# Input.net
KiCad netlist of a schematic drawn in Altium Designer
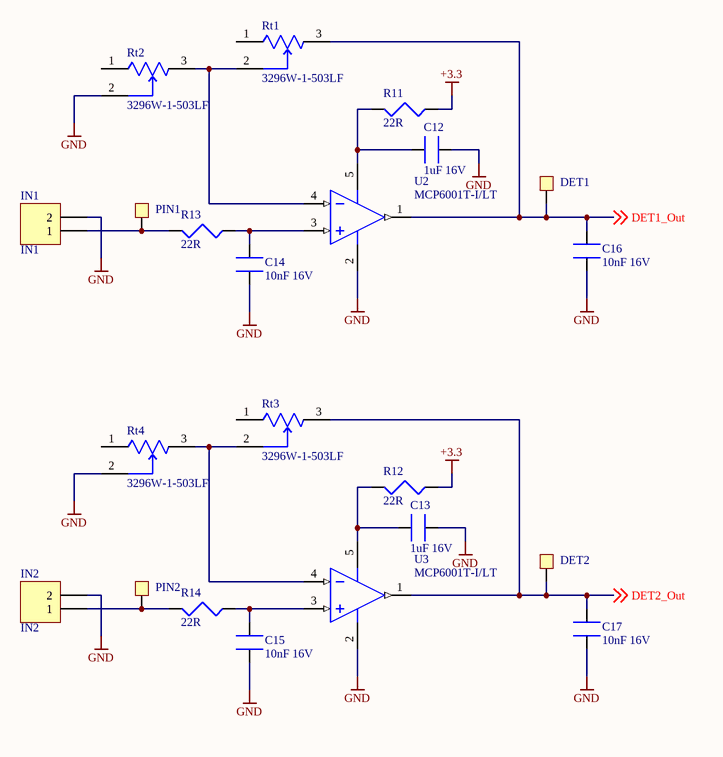
[diagram p0: Input.SchDoc]

(export (version "E")
  (design (tool "Eeschema 10.0.6"))
  (components
    (comp (ref "C12") (value "1uF 16V") (footprint "0805_C") (libsource (lib "Schlib1") (part "Cap")))
    (comp (ref "C13") (value "1uF 16V") (footprint "0805_C") (libsource (lib "Schlib1") (part "Cap")))
    (comp (ref "C14") (value "10nF 16V") (footprint "0805_C") (libsource (lib "Schlib1") (part "Cap")))
    (comp (ref "C15") (value "10nF 16V") (footprint "0805_C") (libsource (lib "Schlib1") (part "Cap")))
    (comp (ref "C16") (value "10nF 16V") (footprint "0805_C") (libsource (lib "Schlib1") (part "Cap")))
    (comp (ref "C17") (value "10nF 16V") (footprint "0805_C") (libsource (lib "Schlib1") (part "Cap")))
    (comp (ref "DET1") (value "Point") (footprint "Test_Point") (libsource (lib "Schlib1") (part "Point")))
    (comp (ref "DET2") (value "Point") (footprint "Test_Point") (libsource (lib "Schlib1") (part "Point")))
    (comp (ref "IN1")
      (value "IN1")
      (footprint "HDR1X2")
      (description "Header, 2-Pin")
      (fields (field (name "PUBLISHER") "Altium Limited"))
      (libsource (lib "Miscellaneous Connectors") (part "Header 2"))
    )
    (comp (ref "IN2")
      (value "IN2")
      (footprint "HDR1X2")
      (description "Header, 2-Pin")
      (fields (field (name "PUBLISHER") "Altium Limited"))
      (libsource (lib "Miscellaneous Connectors") (part "Header 2"))
    )
    (comp (ref "PIN1") (value "Point") (footprint "Test_Point") (libsource (lib "Schlib1") (part "Point")))
    (comp (ref "PIN2") (value "Point") (footprint "Test_Point") (libsource (lib "Schlib1") (part "Point")))
    (comp (ref "R11") (value "22R") (footprint "0805_R") (libsource (lib "Schlib1") (part "Res")))
    (comp (ref "R12") (value "22R") (footprint "0805_R") (libsource (lib "Schlib1") (part "Res")))
    (comp (ref "R13") (value "22R") (footprint "0805_R") (libsource (lib "Schlib1") (part "Res")))
    (comp (ref "R14") (value "22R") (footprint "0805_R") (libsource (lib "Schlib1") (part "Res")))
    (comp (ref "Rt1")
      (value "3296W-1-503LF")
      (footprint "FP-3296W-MFG")
      (description "TRIMMER 50K OHM 0.5W PC PIN TOP")
      (fields
        (field (name "MANUFACTURER") "Bourns")
        (field (name "OCTOPART") "https://octopart.com/3296w-1-504lf-bourns-143884")
      )
      (libsource (lib "Altium Content Vault") (part "8d460c8a6f7ec10b1759d1b9c49aa93"))
    )
    (comp (ref "Rt2")
      (value "3296W-1-503LF")
      (footprint "FP-3296W-MFG")
      (description "TRIMMER 50K OHM 0.5W PC PIN TOP")
      (fields
        (field (name "MANUFACTURER") "Bourns")
        (field (name "OCTOPART") "https://octopart.com/3296w-1-504lf-bourns-143884")
      )
      (libsource (lib "Altium Content Vault") (part "8d460c8a6f7ec10b1759d1b9c49aa93"))
    )
    (comp (ref "Rt3")
      (value "3296W-1-503LF")
      (footprint "FP-3296W-MFG")
      (description "TRIMMER 50K OHM 0.5W PC PIN TOP")
      (fields
        (field (name "MANUFACTURER") "Bourns")
        (field (name "OCTOPART") "https://octopart.com/3296w-1-504lf-bourns-143884")
      )
      (libsource (lib "Altium Content Vault") (part "8d460c8a6f7ec10b1759d1b9c49aa93"))
    )
    (comp (ref "Rt4")
      (value "3296W-1-503LF")
      (footprint "FP-3296W-MFG")
      (description "TRIMMER 50K OHM 0.5W PC PIN TOP")
      (fields
        (field (name "MANUFACTURER") "Bourns")
        (field (name "OCTOPART") "https://octopart.com/3296w-1-504lf-bourns-143884")
      )
      (libsource (lib "Altium Content Vault") (part "8d460c8a6f7ec10b1759d1b9c49aa93"))
    )
    (comp (ref "U2")
      (value "MCP6001T-I/LT")
      (footprint "SC70-LT5_M")
      (description "1 MHz, Low-Power Operational Amplifier, 5-Pin SC-70, Industrial Temperature, Tape and Reel")
      (libsource (lib "Altium Content Vault") (part "AMP-OPA-MCP6001-SOT5"))
    )
    (comp (ref "U3")
      (value "MCP6001T-I/LT")
      (footprint "SC70-LT5_M")
      (description "1 MHz, Low-Power Operational Amplifier, 5-Pin SC-70, Industrial Temperature, Tape and Reel")
      (libsource (lib "Altium Content Vault") (part "AMP-OPA-MCP6001-SOT5"))
    )
  )
  (nets
    (net (code "1") (name "+3.3") (class "Default")
      (node (ref "R11") (pin "2") (pinfunction "2_2") (pintype "passive"))
      (node (ref "R12") (pin "2") (pinfunction "2_2") (pintype "passive"))
    )
    (net (code "2") (name "DET1_Out") (class "Default")
      (node (ref "C16") (pin "1") (pinfunction "1_1") (pintype "passive"))
      (node (ref "DET1") (pin "1") (pinfunction "1_1") (pintype "passive"))
      (node (ref "Rt1") (pin "3") (pinfunction "CW_3") (pintype "passive"))
      (node (ref "U2") (pin "1") (pinfunction "VOUT_1") (pintype "output"))
    )
    (net (code "3") (name "DET2_Out") (class "Default")
      (node (ref "C17") (pin "1") (pinfunction "1_1") (pintype "passive"))
      (node (ref "DET2") (pin "1") (pinfunction "1_1") (pintype "passive"))
      (node (ref "Rt3") (pin "3") (pinfunction "CW_3") (pintype "passive"))
      (node (ref "U3") (pin "1") (pinfunction "VOUT_1") (pintype "output"))
    )
    (net (code "4") (name "GND") (class "Default")
      (node (ref "C12") (pin "2") (pinfunction "2_2") (pintype "passive"))
      (node (ref "C13") (pin "2") (pinfunction "2_2") (pintype "passive"))
      (node (ref "C14") (pin "2") (pinfunction "2_2") (pintype "passive"))
      (node (ref "C15") (pin "2") (pinfunction "2_2") (pintype "passive"))
      (node (ref "C16") (pin "2") (pinfunction "2_2") (pintype "passive"))
      (node (ref "C17") (pin "2") (pinfunction "2_2") (pintype "passive"))
      (node (ref "IN1") (pin "2") (pinfunction "2_2") (pintype "passive"))
      (node (ref "IN2") (pin "2") (pinfunction "2_2") (pintype "passive"))
      (node (ref "Rt2") (pin "2") (pinfunction "WIPER_2") (pintype "passive"))
      (node (ref "Rt4") (pin "2") (pinfunction "WIPER_2") (pintype "passive"))
      (node (ref "U2") (pin "2") (pinfunction "VSS_2") (pintype "power_in"))
      (node (ref "U3") (pin "2") (pinfunction "VSS_2") (pintype "power_in"))
    )
    (net (code "5") (name "Net-(IN1-Pad1)") (class "Default")
      (node (ref "IN1") (pin "1") (pinfunction "1_1") (pintype "passive"))
      (node (ref "PIN1") (pin "1") (pinfunction "1_1") (pintype "passive"))
      (node (ref "R13") (pin "1") (pinfunction "1_1") (pintype "passive"))
    )
    (net (code "6") (name "Net-(IN2-Pad1)") (class "Default")
      (node (ref "IN2") (pin "1") (pinfunction "1_1") (pintype "passive"))
      (node (ref "PIN2") (pin "1") (pinfunction "1_1") (pintype "passive"))
      (node (ref "R14") (pin "1") (pinfunction "1_1") (pintype "passive"))
    )
    (net (code "7") (name "Net-(Rt1-WIPER)") (class "Default")
      (node (ref "Rt1") (pin "2") (pinfunction "WIPER_2") (pintype "passive"))
      (node (ref "Rt2") (pin "3") (pinfunction "CW_3") (pintype "passive"))
      (node (ref "U2") (pin "4") (pinfunction "VIN-_4") (pintype "input"))
    )
    (net (code "8") (name "Net-(Rt3-WIPER)") (class "Default")
      (node (ref "Rt3") (pin "2") (pinfunction "WIPER_2") (pintype "passive"))
      (node (ref "Rt4") (pin "3") (pinfunction "CW_3") (pintype "passive"))
      (node (ref "U3") (pin "4") (pinfunction "VIN-_4") (pintype "input"))
    )
    (net (code "9") (name "Net-(U2-VDD)") (class "Default")
      (node (ref "C12") (pin "1") (pinfunction "1_1") (pintype "passive"))
      (node (ref "R11") (pin "1") (pinfunction "1_1") (pintype "passive"))
      (node (ref "U2") (pin "5") (pinfunction "VDD_5") (pintype "power_in"))
    )
    (net (code "10") (name "Net-(U2-VIN+)") (class "Default")
      (node (ref "C14") (pin "1") (pinfunction "1_1") (pintype "passive"))
      (node (ref "R13") (pin "2") (pinfunction "2_2") (pintype "passive"))
      (node (ref "U2") (pin "3") (pinfunction "VIN+_3") (pintype "input"))
    )
    (net (code "11") (name "Net-(U3-VDD)") (class "Default")
      (node (ref "C13") (pin "1") (pinfunction "1_1") (pintype "passive"))
      (node (ref "R12") (pin "1") (pinfunction "1_1") (pintype "passive"))
      (node (ref "U3") (pin "5") (pinfunction "VDD_5") (pintype "power_in"))
    )
    (net (code "12") (name "Net-(U3-VIN+)") (class "Default")
      (node (ref "C15") (pin "1") (pinfunction "1_1") (pintype "passive"))
      (node (ref "R14") (pin "2") (pinfunction "2_2") (pintype "passive"))
      (node (ref "U3") (pin "3") (pinfunction "VIN+_3") (pintype "input"))
    )
    (net (code "13") (name "unconnected-(Rt1-CCW-Pad1)") (class "Default")
      (node (ref "Rt1") (pin "1") (pinfunction "CCW_1") (pintype "passive"))
    )
    (net (code "14") (name "unconnected-(Rt2-CCW-Pad1)") (class "Default")
      (node (ref "Rt2") (pin "1") (pinfunction "CCW_1") (pintype "passive"))
    )
    (net (code "15") (name "unconnected-(Rt3-CCW-Pad1)") (class "Default")
      (node (ref "Rt3") (pin "1") (pinfunction "CCW_1") (pintype "passive"))
    )
    (net (code "16") (name "unconnected-(Rt4-CCW-Pad1)") (class "Default")
      (node (ref "Rt4") (pin "1") (pinfunction "CCW_1") (pintype "passive"))
    )
  )
)
